# AC_board.net
KiCad netlist of a schematic drawn in EAGLE
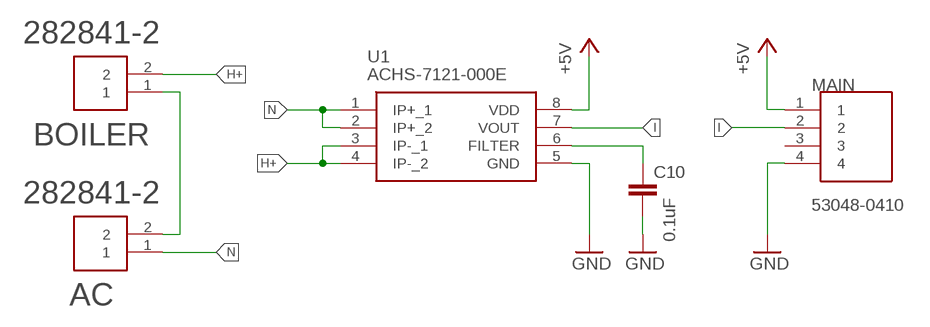
[diagram p0: schematic, sheet 1]

(export (version "E")
  (design (tool "Eeschema 10.0.6"))
  (components
    (comp (ref "AC")
      (value "282841-2")
      (footprint "eagle-import:TE_282841-2")
      (fields (field (name "DIGI-KEY_PART_NUMBER") "A98342-ND") (field (name "MF") "TE Connectivity"))
      (libsource (lib "eagle-import") (part "282841-2"))
    )
    (comp (ref "BOILER")
      (value "282841-2")
      (footprint "eagle-import:TE_282841-2")
      (fields (field (name "DIGI-KEY_PART_NUMBER") "A98342-ND") (field (name "MF") "TE Connectivity"))
      (libsource (lib "eagle-import") (part "282841-2"))
    )
    (comp (ref "C10")
      (value "0.1uF")
      (footprint "eagle-import:C0603K")
      (libsource (lib "eagle-import") (part "C-EUC0603K"))
    )
    (comp (ref "MAIN")
      (value "53048-0410")
      (footprint "eagle-import:530480410")
      (fields (field (name "MOUSER_PART_NUMBER") "538-53048-0410"))
      (libsource (lib "eagle-import") (part "53048-0410"))
    )
    (comp (ref "U1")
      (value "ACHS-7121-000E")
      (footprint "eagle-import:SOIC127P606X204-8N")
      (fields (field (name "MOUSER_PART_NUMBER") "630-ACHS-7121-000E"))
      (libsource (lib "eagle-import") (part "ACHS-7121-000E"))
    )
  )
  (nets
    (net (code "1") (name "+5V") (class "Default")
      (node (ref "MAIN") (pin "1") (pinfunction "1_1") (pintype "bidirectional"))
      (node (ref "U1") (pin "8") (pinfunction "VDD_8") (pintype "bidirectional"))
    )
    (net (code "2") (name "GND") (class "Default")
      (node (ref "C10") (pin "2") (pinfunction "2_2") (pintype "passive"))
      (node (ref "MAIN") (pin "4") (pinfunction "4_4") (pintype "bidirectional"))
      (node (ref "U1") (pin "5") (pinfunction "GND_5") (pintype "bidirectional"))
    )
    (net (code "3") (name "H+") (class "Default")
      (node (ref "BOILER") (pin "2") (pinfunction "2_2") (pintype "passive"))
      (node (ref "U1") (pin "3") (pinfunction "IP-_1_3") (pintype "bidirectional"))
      (node (ref "U1") (pin "4") (pinfunction "IP-_2_4") (pintype "bidirectional"))
    )
    (net (code "4") (name "I") (class "Default")
      (node (ref "MAIN") (pin "2") (pinfunction "2_2") (pintype "bidirectional"))
      (node (ref "U1") (pin "7") (pinfunction "VOUT_7") (pintype "bidirectional"))
    )
    (net (code "5") (name "N") (class "Default")
      (node (ref "AC") (pin "1") (pinfunction "1_1") (pintype "passive"))
      (node (ref "U1") (pin "1") (pinfunction "IP+_1_1") (pintype "bidirectional"))
      (node (ref "U1") (pin "2") (pinfunction "IP+_2_2") (pintype "bidirectional"))
    )
    (net (code "6") (name "Net-(AC-Pad2)") (class "Default")
      (node (ref "AC") (pin "2") (pinfunction "2_2") (pintype "passive"))
      (node (ref "BOILER") (pin "1") (pinfunction "1_1") (pintype "passive"))
    )
    (net (code "7") (name "Net-(U1-FILTER)") (class "Default")
      (node (ref "C10") (pin "1") (pinfunction "1_1") (pintype "passive"))
      (node (ref "U1") (pin "6") (pinfunction "FILTER_6") (pintype "bidirectional"))
    )
    (net (code "8") (name "unconnected-(MAIN-Pad3)") (class "Default")
      (node (ref "MAIN") (pin "3") (pinfunction "3_3") (pintype "bidirectional"))
    )
  )
)
